# M869D.net
KiCad netlist of a schematic drawn in EAGLE
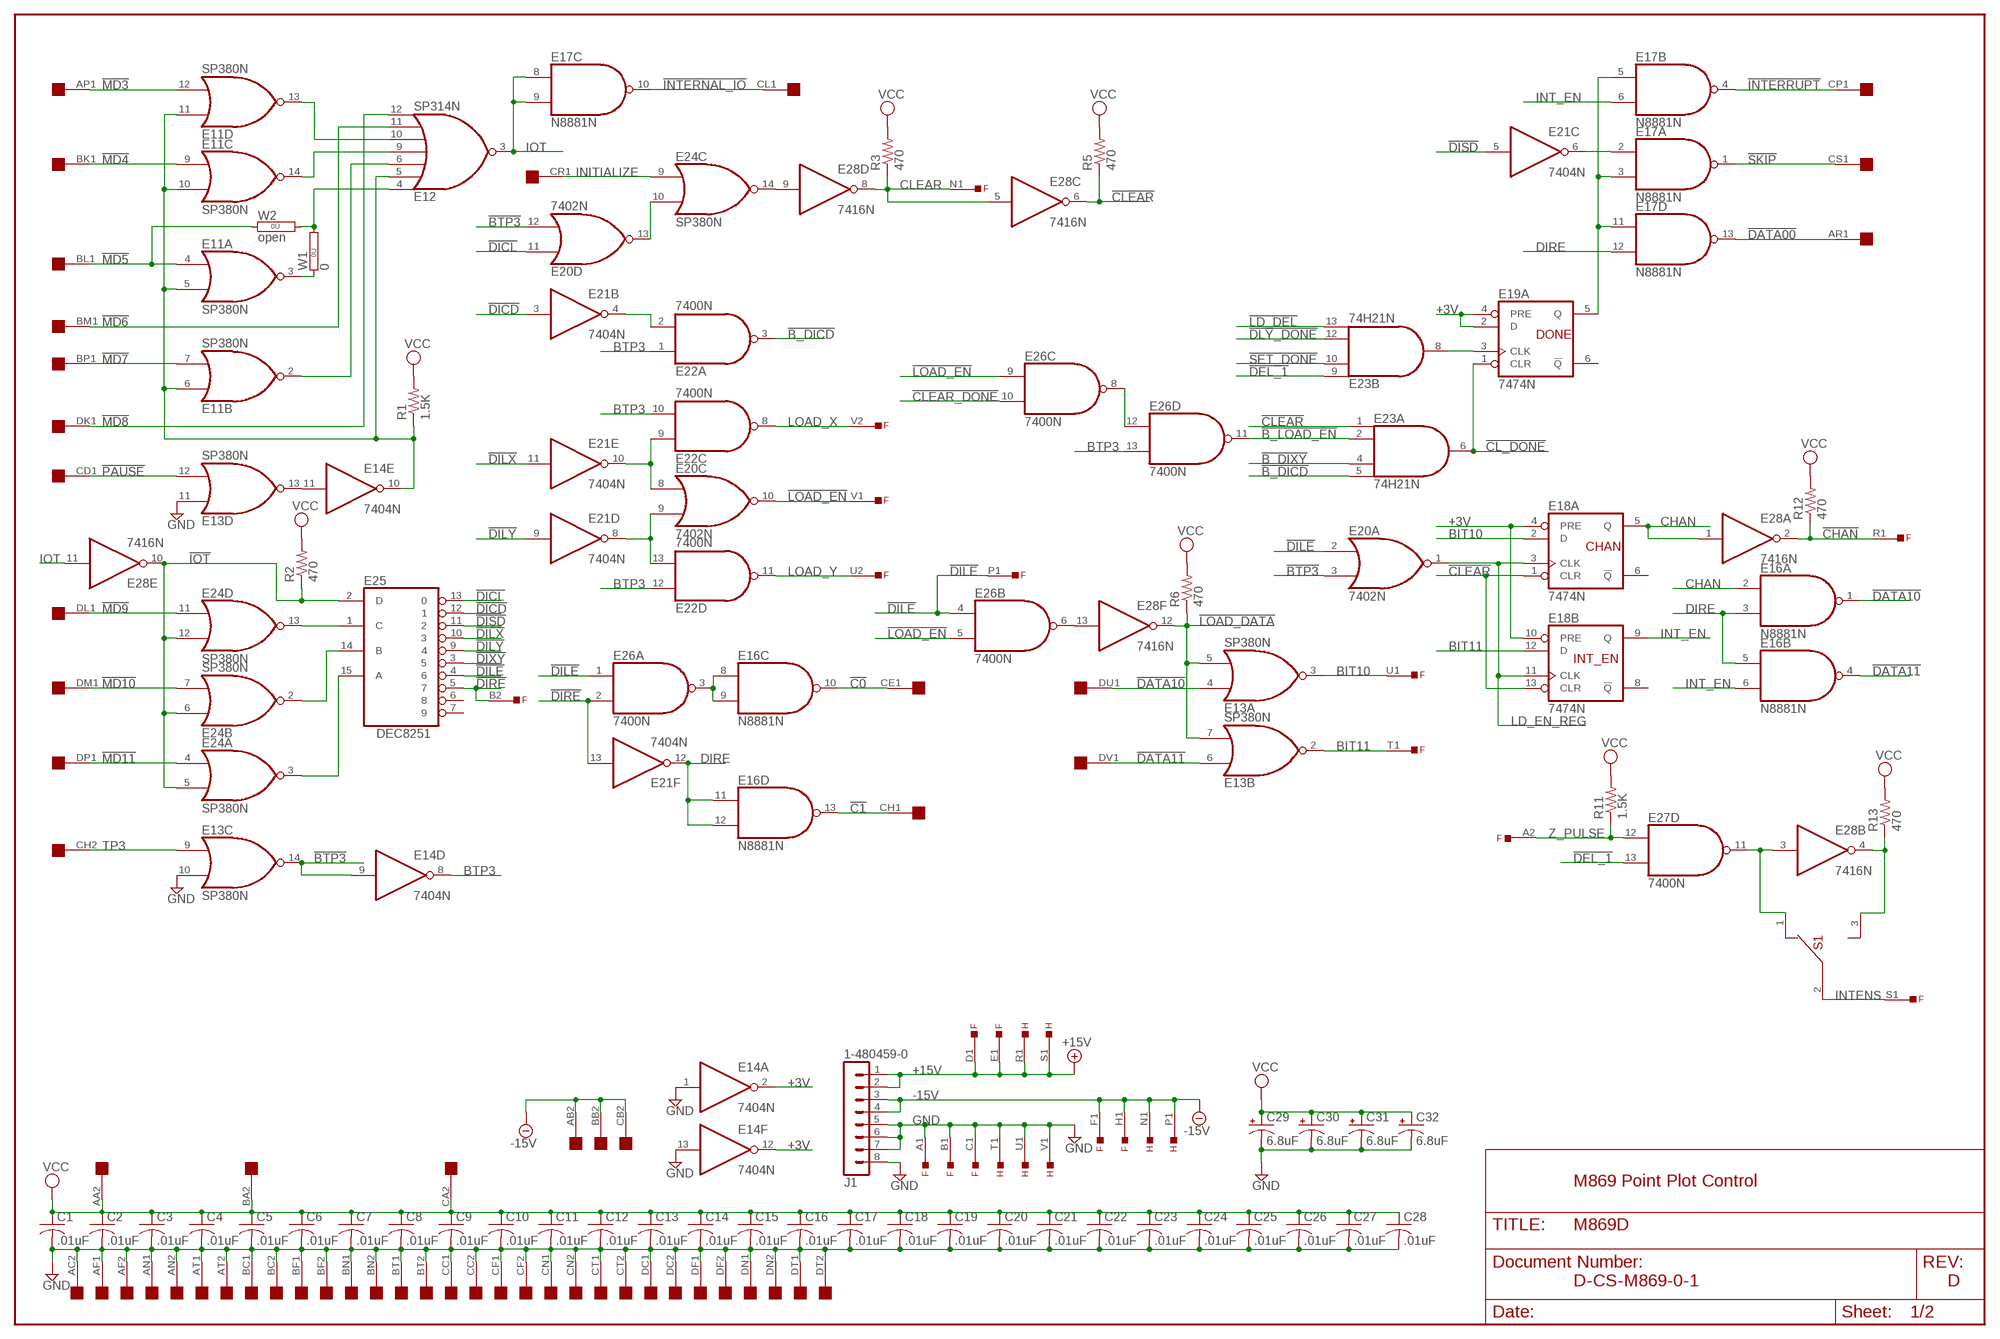
[diagram p0: schematic, sheet 1]
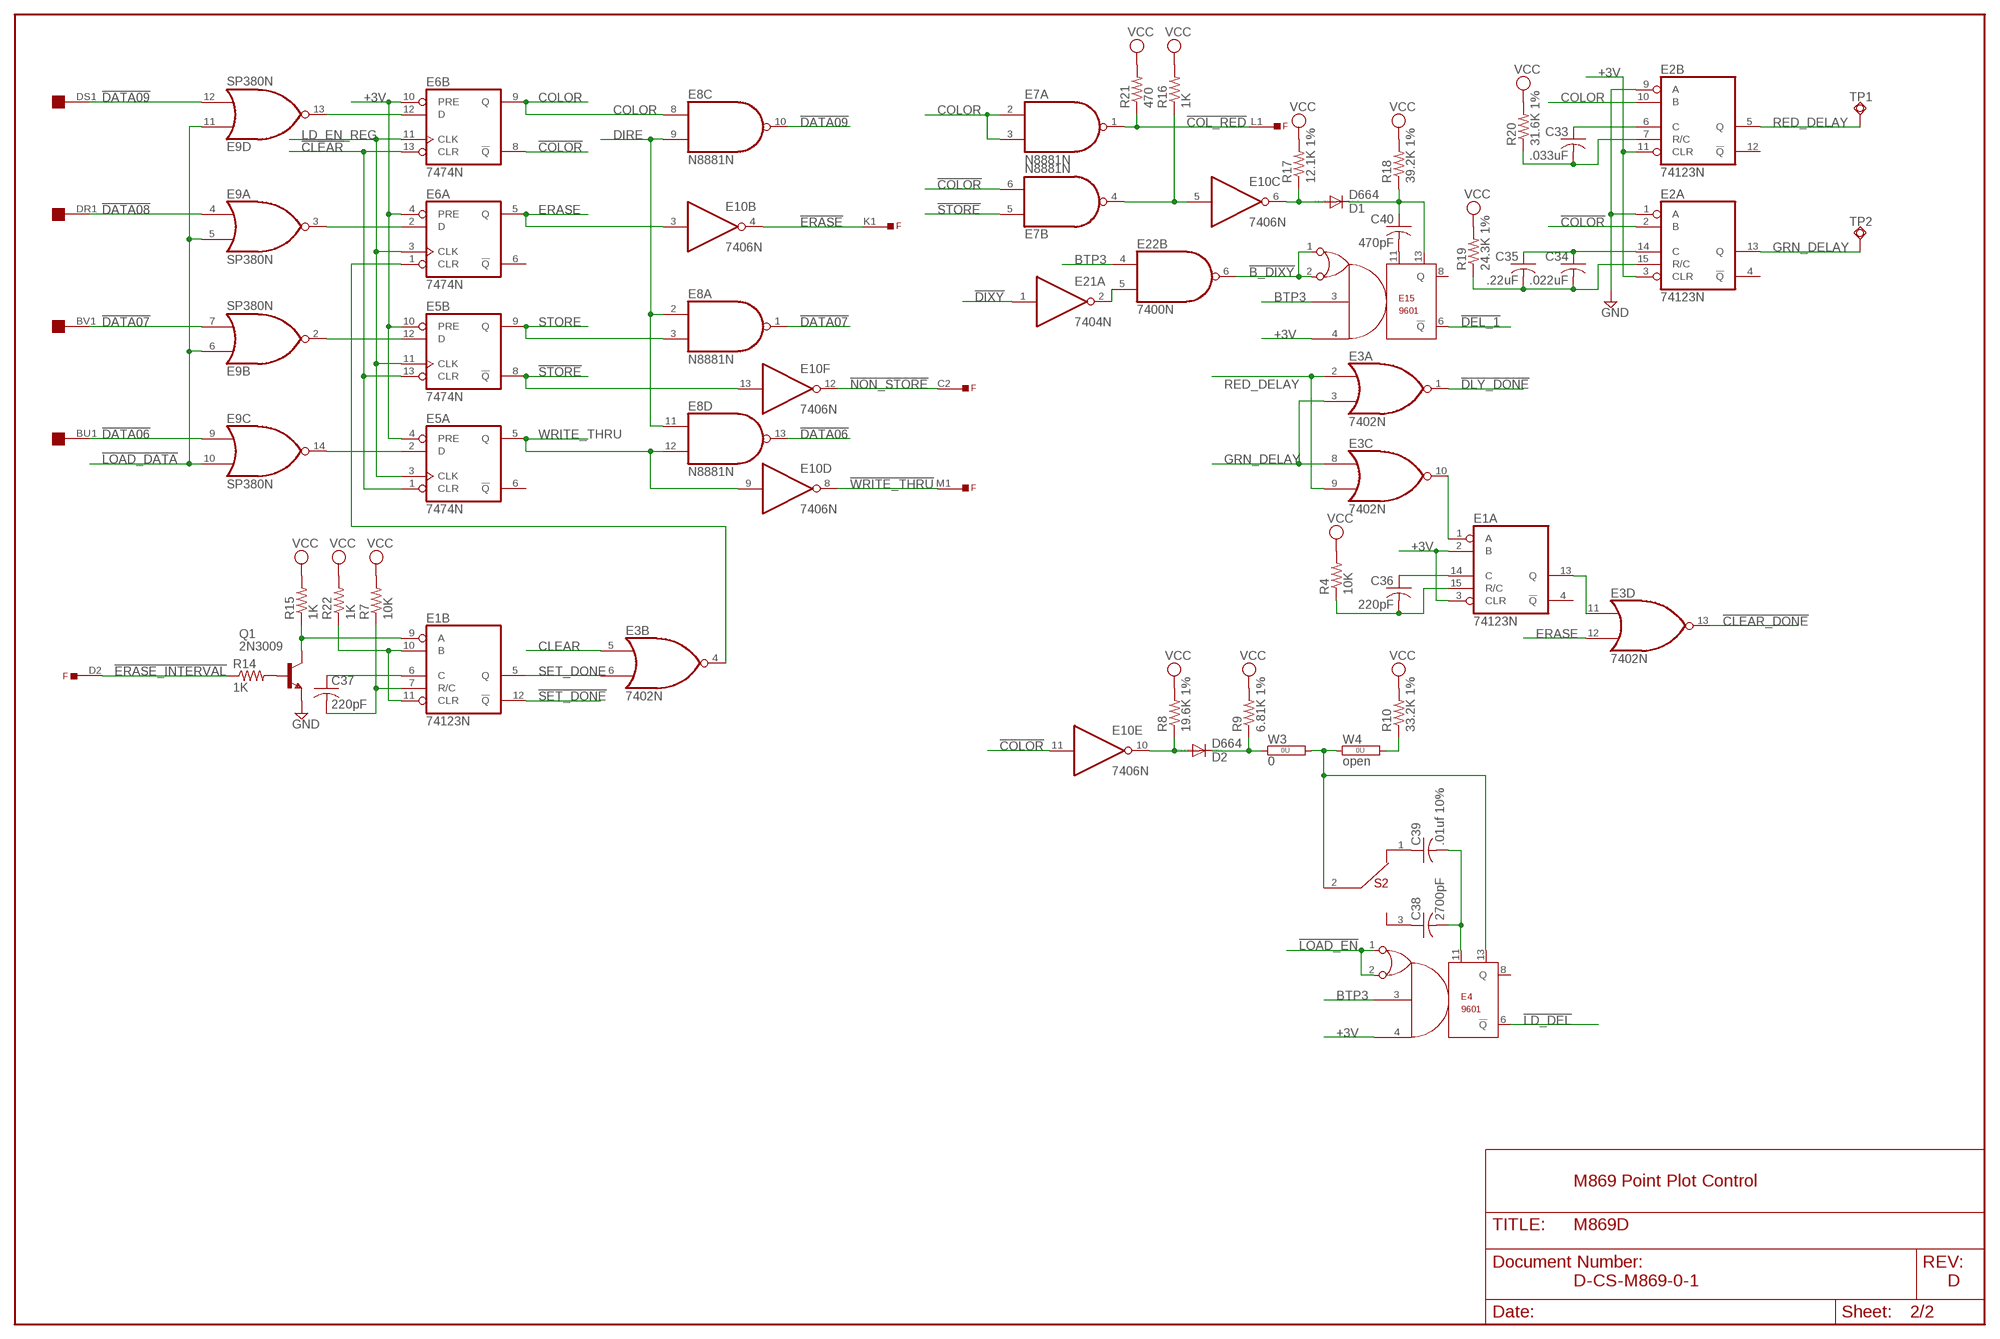
[diagram p1: schematic, sheet 2]

(export (version "E")
  (design (tool "Eeschema 10.0.6"))
  (components
    (comp (ref "C33")
      (value ".033uF")
      (footprint "eagle-import:C325-137X374")
      (libsource (lib "eagle-import") (part "C-US325-137X374"))
    )
    (comp (ref "C34")
      (value ".022uF")
      (footprint "eagle-import:C203-054-229")
      (libsource (lib "eagle-import") (part "C-US8"))
    )
    (comp (ref "C35")
      (value ".22uF")
      (footprint "eagle-import:C203-054-229")
      (libsource (lib "eagle-import") (part "C-US8"))
    )
    (comp (ref "C36")
      (value "220pF")
      (footprint "eagle-import:C063-025X075")
      (libsource (lib "eagle-import") (part "C-US"))
    )
    (comp (ref "C37")
      (value "220pF")
      (footprint "eagle-import:C063-025X075")
      (libsource (lib "eagle-import") (part "C-US"))
    )
    (comp (ref "C38")
      (value "2700pF")
      (footprint "eagle-import:C102-043X133")
      (libsource (lib "eagle-import") (part "C-US102-043X133"))
    )
    (comp (ref "C39")
      (value ".01uf 10%")
      (footprint "eagle-import:C063-025X075")
      (libsource (lib "eagle-import") (part "C-US"))
    )
    (comp (ref "C40")
      (value "470pF")
      (footprint "eagle-import:C063-025X075")
      (libsource (lib "eagle-import") (part "C-US"))
    )
    (comp (ref "D1")
      (value "D664")
      (footprint "eagle-import:DO35-10")
      (libsource (lib "eagle-import") (part "DIODE-DO35-10"))
    )
    (comp (ref "D2")
      (value "D664")
      (footprint "eagle-import:DO35-10")
      (libsource (lib "eagle-import") (part "DIODE-DO35-10"))
    )
    (comp (ref "E1")
      (value "74123N")
      (footprint "eagle-import:DIL16")
      (libsource (lib "eagle-import") (part "74123N"))
    )
    (comp (ref "E2")
      (value "74123N")
      (footprint "eagle-import:DIL16")
      (libsource (lib "eagle-import") (part "74123N"))
    )
    (comp (ref "E3")
      (value "7402N")
      (footprint "eagle-import:DIL14")
      (libsource (lib "eagle-import") (part "7402N"))
    )
    (comp (ref "E4")
      (value "9601")
      (footprint "eagle-import:DIL14")
      (libsource (lib "eagle-import") (part "9601"))
    )
    (comp (ref "E5")
      (value "7474N")
      (footprint "eagle-import:DIL14")
      (libsource (lib "eagle-import") (part "7474NS"))
    )
    (comp (ref "E6")
      (value "7474N")
      (footprint "eagle-import:DIL14")
      (libsource (lib "eagle-import") (part "7474NS"))
    )
    (comp (ref "E7")
      (value "N8881N")
      (footprint "eagle-import:DIL14")
      (libsource (lib "eagle-import") (part "N8881N"))
    )
    (comp (ref "E8")
      (value "N8881N")
      (footprint "eagle-import:DIL14")
      (libsource (lib "eagle-import") (part "N8881N"))
    )
    (comp (ref "E9")
      (value "SP380N")
      (footprint "eagle-import:DIL14")
      (libsource (lib "eagle-import") (part "SP380N"))
    )
    (comp (ref "E10")
      (value "7406N")
      (footprint "eagle-import:DIL14")
      (libsource (lib "eagle-import") (part "7406N"))
    )
    (comp (ref "E15")
      (value "9601")
      (footprint "eagle-import:DIL14")
      (libsource (lib "eagle-import") (part "9601"))
    )
    (comp (ref "E21")
      (value "7404N")
      (footprint "eagle-import:DIL14")
      (libsource (lib "eagle-import") (part "7404N"))
    )
    (comp (ref "E22")
      (value "7400N")
      (footprint "eagle-import:DIL14")
      (libsource (lib "eagle-import") (part "7400N"))
    )
    (comp (ref "F")
      (value "EDGE-TOP")
      (footprint "eagle-import:EDGE-CON2")
      (libsource (lib "eagle-import") (part "EDGE-TOP"))
    )
    (comp (ref "OMNIBUS")
      (value "QUAD")
      (footprint "eagle-import:EDGE-CON8")
      (libsource (lib "eagle-import") (part "QUAD"))
    )
    (comp (ref "Q1")
      (value "2N3009")
      (footprint "eagle-import:TO18-")
      (libsource (lib "eagle-import") (part "-NPN-TO18-"))
    )
    (comp (ref "R4")
      (value "10K")
      (footprint "eagle-import:0207_10")
      (libsource (lib "eagle-import") (part "R-US_0207/10"))
    )
    (comp (ref "R7")
      (value "10K")
      (footprint "eagle-import:0207_10")
      (libsource (lib "eagle-import") (part "R-US_0207/10"))
    )
    (comp (ref "R8")
      (value "19.6K 1%")
      (footprint "eagle-import:0207_15")
      (libsource (lib "eagle-import") (part "R-US_0207/15"))
    )
    (comp (ref "R9")
      (value "6.81K 1%")
      (footprint "eagle-import:0207_15")
      (libsource (lib "eagle-import") (part "R-US_0207/15"))
    )
    (comp (ref "R10")
      (value "33.2K 1%")
      (footprint "eagle-import:0207_15")
      (libsource (lib "eagle-import") (part "R-US_0207/15"))
    )
    (comp (ref "R14")
      (value "1K")
      (footprint "eagle-import:0207_10")
      (libsource (lib "eagle-import") (part "R-US_0207/10"))
    )
    (comp (ref "R15")
      (value "1K")
      (footprint "eagle-import:0207_10")
      (libsource (lib "eagle-import") (part "R-US_0207/10"))
    )
    (comp (ref "R16")
      (value "1K")
      (footprint "eagle-import:0207_10")
      (libsource (lib "eagle-import") (part "R-US_0207/10"))
    )
    (comp (ref "R17")
      (value "12.1K 1%")
      (footprint "eagle-import:0207_15")
      (libsource (lib "eagle-import") (part "R-US_0207/15"))
    )
    (comp (ref "R18")
      (value "39.2K 1%")
      (footprint "eagle-import:0207_15")
      (libsource (lib "eagle-import") (part "R-US_0207/15"))
    )
    (comp (ref "R19")
      (value "24.3K 1%")
      (footprint "eagle-import:0207_15")
      (libsource (lib "eagle-import") (part "R-US_0207/15"))
    )
    (comp (ref "R20")
      (value "31.6K 1%")
      (footprint "eagle-import:0207_15")
      (libsource (lib "eagle-import") (part "R-US_0207/15"))
    )
    (comp (ref "R21")
      (value "470")
      (footprint "eagle-import:0207_10")
      (libsource (lib "eagle-import") (part "R-US_0207/10"))
    )
    (comp (ref "R22")
      (value "1K")
      (footprint "eagle-import:0207_10")
      (libsource (lib "eagle-import") (part "R-US_0207/10"))
    )
    (comp (ref "S2")
      (value "12-09698")
      (footprint "eagle-import:23-021")
      (libsource (lib "eagle-import") (part "12-09698"))
    )
    (comp (ref "TP1")
      (value "TPSQPAD1-17")
      (footprint "eagle-import:P1-17")
      (libsource (lib "eagle-import") (part "TPSQPAD1-17"))
    )
    (comp (ref "TP2")
      (value "TPSQPAD1-17")
      (footprint "eagle-import:P1-17")
      (libsource (lib "eagle-import") (part "TPSQPAD1-17"))
    )
    (comp (ref "W3")
      (value "0")
      (footprint "eagle-import:0R_10")
      (libsource (lib "eagle-import") (part "0R"))
    )
    (comp (ref "W4")
      (value "open")
      (footprint "eagle-import:0R_10")
      (libsource (lib "eagle-import") (part "0R"))
    )
    (comp (ref "C1")
      (value ".01uF")
      (footprint "eagle-import:C063-025X075")
      (libsource (lib "eagle-import") (part "C-US"))
    )
    (comp (ref "C2")
      (value ".01uF")
      (footprint "eagle-import:C063-025X075")
      (libsource (lib "eagle-import") (part "C-US"))
    )
    (comp (ref "C3")
      (value ".01uF")
      (footprint "eagle-import:C063-025X075")
      (libsource (lib "eagle-import") (part "C-US"))
    )
    (comp (ref "C4")
      (value ".01uF")
      (footprint "eagle-import:C063-025X075")
      (libsource (lib "eagle-import") (part "C-US"))
    )
    (comp (ref "C5")
      (value ".01uF")
      (footprint "eagle-import:C063-025X075")
      (libsource (lib "eagle-import") (part "C-US"))
    )
    (comp (ref "C6")
      (value ".01uF")
      (footprint "eagle-import:C063-025X075")
      (libsource (lib "eagle-import") (part "C-US"))
    )
    (comp (ref "C7")
      (value ".01uF")
      (footprint "eagle-import:C063-025X075")
      (libsource (lib "eagle-import") (part "C-US"))
    )
    (comp (ref "C8")
      (value ".01uF")
      (footprint "eagle-import:C063-025X075")
      (libsource (lib "eagle-import") (part "C-US"))
    )
    (comp (ref "C9")
      (value ".01uF")
      (footprint "eagle-import:C063-025X075")
      (libsource (lib "eagle-import") (part "C-US"))
    )
    (comp (ref "C10")
      (value ".01uF")
      (footprint "eagle-import:C063-025X075")
      (libsource (lib "eagle-import") (part "C-US"))
    )
    (comp (ref "C11")
      (value ".01uF")
      (footprint "eagle-import:C063-025X075")
      (libsource (lib "eagle-import") (part "C-US"))
    )
    (comp (ref "C12")
      (value ".01uF")
      (footprint "eagle-import:C063-025X075")
      (libsource (lib "eagle-import") (part "C-US"))
    )
    (comp (ref "C13")
      (value ".01uF")
      (footprint "eagle-import:C063-025X075")
      (libsource (lib "eagle-import") (part "C-US"))
    )
    (comp (ref "C14")
      (value ".01uF")
      (footprint "eagle-import:C063-025X075")
      (libsource (lib "eagle-import") (part "C-US"))
    )
    (comp (ref "C15")
      (value ".01uF")
      (footprint "eagle-import:C063-025X075")
      (libsource (lib "eagle-import") (part "C-US"))
    )
    (comp (ref "C16")
      (value ".01uF")
      (footprint "eagle-import:C063-025X075")
      (libsource (lib "eagle-import") (part "C-US"))
    )
    (comp (ref "C17")
      (value ".01uF")
      (footprint "eagle-import:C063-025X075")
      (libsource (lib "eagle-import") (part "C-US"))
    )
    (comp (ref "C18")
      (value ".01uF")
      (footprint "eagle-import:C063-025X075")
      (libsource (lib "eagle-import") (part "C-US"))
    )
    (comp (ref "C19")
      (value ".01uF")
      (footprint "eagle-import:C063-025X075")
      (libsource (lib "eagle-import") (part "C-US"))
    )
    (comp (ref "C20")
      (value ".01uF")
      (footprint "eagle-import:C063-025X075")
      (libsource (lib "eagle-import") (part "C-US"))
    )
    (comp (ref "C21")
      (value ".01uF")
      (footprint "eagle-import:C063-025X075")
      (libsource (lib "eagle-import") (part "C-US"))
    )
    (comp (ref "C22")
      (value ".01uF")
      (footprint "eagle-import:C063-025X075")
      (libsource (lib "eagle-import") (part "C-US"))
    )
    (comp (ref "C23")
      (value ".01uF")
      (footprint "eagle-import:C063-025X075")
      (libsource (lib "eagle-import") (part "C-US"))
    )
    (comp (ref "C24")
      (value ".01uF")
      (footprint "eagle-import:C063-025X075")
      (libsource (lib "eagle-import") (part "C-US"))
    )
    (comp (ref "C25")
      (value ".01uF")
      (footprint "eagle-import:C063-025X075")
      (libsource (lib "eagle-import") (part "C-US"))
    )
    (comp (ref "C26")
      (value ".01uF")
      (footprint "eagle-import:C063-025X075")
      (libsource (lib "eagle-import") (part "C-US"))
    )
    (comp (ref "C27")
      (value ".01uF")
      (footprint "eagle-import:C063-025X075")
      (libsource (lib "eagle-import") (part "C-US"))
    )
    (comp (ref "C28")
      (value ".01uF")
      (footprint "eagle-import:C063-025X075")
      (libsource (lib "eagle-import") (part "C-US"))
    )
    (comp (ref "C29")
      (value "6.8uF")
      (footprint "eagle-import:E12-8")
      (libsource (lib "eagle-import") (part "CPOL-USE20-8AXIAL"))
    )
    (comp (ref "C30")
      (value "6.8uF")
      (footprint "eagle-import:E12-8")
      (libsource (lib "eagle-import") (part "CPOL-USE20-8AXIAL"))
    )
    (comp (ref "C31")
      (value "6.8uF")
      (footprint "eagle-import:E12-8")
      (libsource (lib "eagle-import") (part "CPOL-USE20-8AXIAL"))
    )
    (comp (ref "C32")
      (value "6.8uF")
      (footprint "eagle-import:E12-8")
      (libsource (lib "eagle-import") (part "CPOL-USE20-8AXIAL"))
    )
    (comp (ref "E11")
      (value "SP380N")
      (footprint "eagle-import:DIL14")
      (libsource (lib "eagle-import") (part "SP380N"))
    )
    (comp (ref "E12")
      (value "SP314N")
      (footprint "eagle-import:DIL14")
      (libsource (lib "eagle-import") (part "SP314N"))
    )
    (comp (ref "E13")
      (value "SP380N")
      (footprint "eagle-import:DIL14")
      (libsource (lib "eagle-import") (part "SP380N"))
    )
    (comp (ref "E14")
      (value "7404N")
      (footprint "eagle-import:DIL14")
      (libsource (lib "eagle-import") (part "7404N"))
    )
    (comp (ref "E16")
      (value "N8881N")
      (footprint "eagle-import:DIL14")
      (libsource (lib "eagle-import") (part "N8881N"))
    )
    (comp (ref "E17")
      (value "N8881N")
      (footprint "eagle-import:DIL14")
      (libsource (lib "eagle-import") (part "N8881N"))
    )
    (comp (ref "E18")
      (value "7474N")
      (footprint "eagle-import:DIL14")
      (libsource (lib "eagle-import") (part "7474NS"))
    )
    (comp (ref "E19")
      (value "7474N")
      (footprint "eagle-import:DIL14")
      (libsource (lib "eagle-import") (part "7474NS"))
    )
    (comp (ref "E20")
      (value "7402N")
      (footprint "eagle-import:DIL14")
      (libsource (lib "eagle-import") (part "7402N"))
    )
    (comp (ref "E23")
      (value "74H21N")
      (footprint "eagle-import:DIL14")
      (libsource (lib "eagle-import") (part "7421NLS"))
    )
    (comp (ref "E24")
      (value "SP380N")
      (footprint "eagle-import:DIL14")
      (libsource (lib "eagle-import") (part "SP380N"))
    )
    (comp (ref "E25")
      (value "DEC8251")
      (footprint "eagle-import:DIL16")
      (libsource (lib "eagle-import") (part "DEC8251"))
    )
    (comp (ref "E26")
      (value "7400N")
      (footprint "eagle-import:DIL14")
      (libsource (lib "eagle-import") (part "7400N"))
    )
    (comp (ref "E27")
      (value "7400N")
      (footprint "eagle-import:DIL14")
      (libsource (lib "eagle-import") (part "7400N"))
    )
    (comp (ref "E28")
      (value "7416N")
      (footprint "eagle-import:DIL14")
      (libsource (lib "eagle-import") (part "7416N"))
    )
    (comp (ref "H")
      (value "EDGE-TOP")
      (footprint "eagle-import:EDGE-CON2")
      (libsource (lib "eagle-import") (part "EDGE-TOP"))
    )
    (comp (ref "J1")
      (value "1-480459-0")
      (footprint "eagle-import:1-480459-0")
      (libsource (lib "eagle-import") (part "1-480459-0"))
    )
    (comp (ref "R1")
      (value "1.5K")
      (footprint "eagle-import:0207_10")
      (libsource (lib "eagle-import") (part "R-US_0207/10"))
    )
    (comp (ref "R2")
      (value "470")
      (footprint "eagle-import:0207_10")
      (libsource (lib "eagle-import") (part "R-US_0207/10"))
    )
    (comp (ref "R3")
      (value "470")
      (footprint "eagle-import:0207_10")
      (libsource (lib "eagle-import") (part "R-US_0207/10"))
    )
    (comp (ref "R5")
      (value "470")
      (footprint "eagle-import:0207_10")
      (libsource (lib "eagle-import") (part "R-US_0207/10"))
    )
    (comp (ref "R6")
      (value "470")
      (footprint "eagle-import:0207_10")
      (libsource (lib "eagle-import") (part "R-US_0207/10"))
    )
    (comp (ref "R11")
      (value "1.5K")
      (footprint "eagle-import:0207_10")
      (libsource (lib "eagle-import") (part "R-US_0207/10"))
    )
    (comp (ref "R12")
      (value "470")
      (footprint "eagle-import:0207_10")
      (libsource (lib "eagle-import") (part "R-US_0207/10"))
    )
    (comp (ref "R13")
      (value "470")
      (footprint "eagle-import:0207_10")
      (libsource (lib "eagle-import") (part "R-US_0207/10"))
    )
    (comp (ref "S1")
      (value "12-09698")
      (footprint "eagle-import:23-021")
      (libsource (lib "eagle-import") (part "12-09698"))
    )
    (comp (ref "W1")
      (value "0")
      (footprint "eagle-import:0R_10")
      (libsource (lib "eagle-import") (part "0R"))
    )
    (comp (ref "W2")
      (value "open")
      (footprint "eagle-import:0R_10")
      (libsource (lib "eagle-import") (part "0R"))
    )
  )
  (nets
    (net (code "1") (name "+3V") (class "Default")
      (node (ref "E1") (pin "2") (pinfunction "B_2") (pintype "input"))
      (node (ref "E1") (pin "3") (pinfunction "CLR_3") (pintype "input"))
      (node (ref "E14") (pin "12") (pinfunction "O_12") (pintype "output"))
      (node (ref "E14") (pin "2") (pinfunction "O_2") (pintype "output"))
      (node (ref "E15") (pin "4") (pinfunction "P$4_4") (pintype "input"))
      (node (ref "E18") (pin "10") (pinfunction "PRE_10") (pintype "input"))
      (node (ref "E18") (pin "4") (pinfunction "PRE_4") (pintype "input"))
      (node (ref "E19") (pin "2") (pinfunction "D_2") (pintype "input"))
      (node (ref "E19") (pin "4") (pinfunction "PRE_4") (pintype "input"))
      (node (ref "E2") (pin "11") (pinfunction "CLR_11") (pintype "input"))
      (node (ref "E2") (pin "3") (pinfunction "CLR_3") (pintype "input"))
      (node (ref "E4") (pin "4") (pinfunction "P$4_4") (pintype "input"))
      (node (ref "E5") (pin "10") (pinfunction "PRE_10") (pintype "input"))
      (node (ref "E5") (pin "4") (pinfunction "PRE_4") (pintype "input"))
      (node (ref "E6") (pin "10") (pinfunction "PRE_10") (pintype "input"))
      (node (ref "E6") (pin "4") (pinfunction "PRE_4") (pintype "input"))
    )
    (net (code "2") (name "+15V") (class "Default")
      (node (ref "F") (pin "D1") (pinfunction "P_D1") (pintype "passive"))
      (node (ref "F") (pin "E1") (pinfunction "P_E1") (pintype "passive"))
      (node (ref "H") (pin "R1") (pinfunction "P_R1") (pintype "passive"))
      (node (ref "H") (pin "S1") (pinfunction "P_S1") (pintype "passive"))
      (node (ref "J1") (pin "1") (pinfunction "1_1") (pintype "passive"))
      (node (ref "J1") (pin "2") (pinfunction "2_2") (pintype "passive"))
    )
    (net (code "3") (name "-15V") (class "Default")
      (node (ref "F") (pin "F1") (pinfunction "P_F1") (pintype "passive"))
      (node (ref "F") (pin "H1") (pinfunction "P_H1") (pintype "passive"))
      (node (ref "H") (pin "N1") (pinfunction "P_N1") (pintype "passive"))
      (node (ref "H") (pin "P1") (pinfunction "P_P1") (pintype "passive"))
      (node (ref "J1") (pin "3") (pinfunction "3_3") (pintype "passive"))
      (node (ref "J1") (pin "4") (pinfunction "4_4") (pintype "passive"))
      (node (ref "OMNIBUS") (pin "AB2") (pinfunction "1_AB2") (pintype "bidirectional"))
      (node (ref "OMNIBUS") (pin "BB2") (pinfunction "1_BB2") (pintype "bidirectional"))
      (node (ref "OMNIBUS") (pin "CB2") (pinfunction "1_CB2") (pintype "bidirectional"))
    )
    (net (code "4") (name "BIT10") (class "Default")
      (node (ref "E13") (pin "3") (pinfunction "O_3") (pintype "output"))
      (node (ref "E18") (pin "2") (pinfunction "D_2") (pintype "input"))
      (node (ref "F") (pin "U1") (pinfunction "P_U1") (pintype "passive"))
    )
    (net (code "5") (name "BIT11") (class "Default")
      (node (ref "E13") (pin "2") (pinfunction "O_2") (pintype "output"))
      (node (ref "E18") (pin "12") (pinfunction "D_12") (pintype "input"))
      (node (ref "F") (pin "T1") (pinfunction "P_T1") (pintype "passive"))
    )
    (net (code "6") (name "BTP3") (class "Default")
      (node (ref "E14") (pin "8") (pinfunction "O_8") (pintype "output"))
      (node (ref "E15") (pin "3") (pinfunction "P$3_3") (pintype "input"))
      (node (ref "E22") (pin "1") (pinfunction "I0_1") (pintype "input"))
      (node (ref "E22") (pin "10") (pinfunction "I1_10") (pintype "input"))
      (node (ref "E22") (pin "12") (pinfunction "I0_12") (pintype "input"))
      (node (ref "E22") (pin "4") (pinfunction "I0_4") (pintype "input"))
      (node (ref "E26") (pin "13") (pinfunction "I1_13") (pintype "input"))
      (node (ref "E4") (pin "3") (pinfunction "P$3_3") (pintype "input"))
    )
    (net (code "7") (name "CHAN") (class "Default")
      (node (ref "E16") (pin "2") (pinfunction "I0_2") (pintype "input"))
      (node (ref "E18") (pin "5") (pinfunction "Q_5") (pintype "output"))
      (node (ref "E28") (pin "1") (pinfunction "I_1") (pintype "input"))
    )
    (net (code "8") (name "CLEAR") (class "Default")
      (node (ref "E28") (pin "5") (pinfunction "I_5") (pintype "input"))
      (node (ref "E28") (pin "8") (pinfunction "O_8") (pintype "open_collector"))
      (node (ref "E3") (pin "5") (pinfunction "I0_5") (pintype "input"))
      (node (ref "F") (pin "N1") (pinfunction "P_N1") (pintype "passive"))
      (node (ref "R3") (pin "1") (pinfunction "1_1") (pintype "passive"))
    )
    (net (code "9") (name "COLOR") (class "Default")
      (node (ref "E2") (pin "10") (pinfunction "B_10") (pintype "input"))
      (node (ref "E6") (pin "9") (pinfunction "Q_9") (pintype "output"))
      (node (ref "E7") (pin "2") (pinfunction "I0_2") (pintype "input"))
      (node (ref "E7") (pin "3") (pinfunction "I1_3") (pintype "input"))
      (node (ref "E8") (pin "8") (pinfunction "I0_8") (pintype "input"))
    )
    (net (code "10") (name "DIRE") (class "Default")
      (node (ref "E16") (pin "11") (pinfunction "I0_11") (pintype "input"))
      (node (ref "E16") (pin "12") (pinfunction "I1_12") (pintype "input"))
      (node (ref "E16") (pin "3") (pinfunction "I1_3") (pintype "input"))
      (node (ref "E16") (pin "5") (pinfunction "I0_5") (pintype "input"))
      (node (ref "E17") (pin "12") (pinfunction "I1_12") (pintype "input"))
      (node (ref "E21") (pin "12") (pinfunction "O_12") (pintype "output"))
      (node (ref "E8") (pin "11") (pinfunction "I0_11") (pintype "input"))
      (node (ref "E8") (pin "2") (pinfunction "I0_2") (pintype "input"))
      (node (ref "E8") (pin "9") (pinfunction "I1_9") (pintype "input"))
    )
    (net (code "11") (name "ERASE") (class "Default")
      (node (ref "E10") (pin "3") (pinfunction "I_3") (pintype "input"))
      (node (ref "E3") (pin "12") (pinfunction "I1_12") (pintype "input"))
      (node (ref "E6") (pin "5") (pinfunction "Q_5") (pintype "output"))
    )
    (net (code "12") (name "GND") (class "Default")
      (node (ref "C1") (pin "2") (pinfunction "2_2") (pintype "passive"))
      (node (ref "C10") (pin "2") (pinfunction "2_2") (pintype "passive"))
      (node (ref "C11") (pin "2") (pinfunction "2_2") (pintype "passive"))
      (node (ref "C12") (pin "2") (pinfunction "2_2") (pintype "passive"))
      (node (ref "C13") (pin "2") (pinfunction "2_2") (pintype "passive"))
      (node (ref "C14") (pin "2") (pinfunction "2_2") (pintype "passive"))
      (node (ref "C15") (pin "2") (pinfunction "2_2") (pintype "passive"))
      (node (ref "C16") (pin "2") (pinfunction "2_2") (pintype "passive"))
      (node (ref "C17") (pin "2") (pinfunction "2_2") (pintype "passive"))
      (node (ref "C18") (pin "2") (pinfunction "2_2") (pintype "passive"))
      (node (ref "C19") (pin "2") (pinfunction "2_2") (pintype "passive"))
      (node (ref "C2") (pin "2") (pinfunction "2_2") (pintype "passive"))
      (node (ref "C20") (pin "2") (pinfunction "2_2") (pintype "passive"))
      (node (ref "C21") (pin "2") (pinfunction "2_2") (pintype "passive"))
      (node (ref "C22") (pin "2") (pinfunction "2_2") (pintype "passive"))
      (node (ref "C23") (pin "2") (pinfunction "2_2") (pintype "passive"))
      (node (ref "C24") (pin "2") (pinfunction "2_2") (pintype "passive"))
      (node (ref "C25") (pin "2") (pinfunction "2_2") (pintype "passive"))
      (node (ref "C26") (pin "2") (pinfunction "2_2") (pintype "passive"))
      (node (ref "C27") (pin "2") (pinfunction "2_2") (pintype "passive"))
      (node (ref "C28") (pin "2") (pinfunction "2_2") (pintype "passive"))
      (node (ref "C29") (pin "-") (pinfunction "-_-") (pintype "passive"))
      (node (ref "C3") (pin "2") (pinfunction "2_2") (pintype "passive"))
      (node (ref "C30") (pin "-") (pinfunction "-_-") (pintype "passive"))
      (node (ref "C31") (pin "-") (pinfunction "-_-") (pintype "passive"))
      (node (ref "C32") (pin "-") (pinfunction "-_-") (pintype "passive"))
      (node (ref "C4") (pin "2") (pinfunction "2_2") (pintype "passive"))
      (node (ref "C5") (pin "2") (pinfunction "2_2") (pintype "passive"))
      (node (ref "C6") (pin "2") (pinfunction "2_2") (pintype "passive"))
      (node (ref "C7") (pin "2") (pinfunction "2_2") (pintype "passive"))
      (node (ref "C8") (pin "2") (pinfunction "2_2") (pintype "passive"))
      (node (ref "C9") (pin "2") (pinfunction "2_2") (pintype "passive"))
      (node (ref "E13") (pin "10") (pinfunction "I1_10") (pintype "input"))
      (node (ref "E13") (pin "11") (pinfunction "I0_11") (pintype "input"))
      (node (ref "E14") (pin "1") (pinfunction "I_1") (pintype "input"))
      (node (ref "E14") (pin "13") (pinfunction "I_13") (pintype "input"))
      (node (ref "E2") (pin "1") (pinfunction "A_1") (pintype "input"))
      (node (ref "E2") (pin "9") (pinfunction "A_9") (pintype "input"))
      (node (ref "F") (pin "A1") (pinfunction "P_A1") (pintype "passive"))
      (node (ref "F") (pin "B1") (pinfunction "P_B1") (pintype "passive"))
      (node (ref "F") (pin "C1") (pinfunction "P_C1") (pintype "passive"))
      (node (ref "H") (pin "T1") (pinfunction "P_T1") (pintype "passive"))
      (node (ref "H") (pin "U1") (pinfunction "P_U1") (pintype "passive"))
      (node (ref "H") (pin "V1") (pinfunction "P_V1") (pintype "passive"))
      (node (ref "J1") (pin "5") (pinfunction "5_5") (pintype "passive"))
      (node (ref "J1") (pin "6") (pinfunction "6_6") (pintype "passive"))
      (node (ref "J1") (pin "7") (pinfunction "7_7") (pintype "passive"))
      (node (ref "J1") (pin "8") (pinfunction "8_8") (pintype "passive"))
      (node (ref "OMNIBUS") (pin "AC2") (pinfunction "1_AC2") (pintype "bidirectional"))
      (node (ref "OMNIBUS") (pin "AF1") (pinfunction "1_AF1") (pintype "bidirectional"))
      (node (ref "OMNIBUS") (pin "AF2") (pinfunction "1_AF2") (pintype "bidirectional"))
      (node (ref "OMNIBUS") (pin "AN1") (pinfunction "1_AN1") (pintype "bidirectional"))
      (node (ref "OMNIBUS") (pin "AN2") (pinfunction "1_AN2") (pintype "bidirectional"))
      (node (ref "OMNIBUS") (pin "AT1") (pinfunction "1_AT1") (pintype "bidirectional"))
      (node (ref "OMNIBUS") (pin "AT2") (pinfunction "1_AT2") (pintype "bidirectional"))
      (node (ref "OMNIBUS") (pin "BC1") (pinfunction "1_BC1") (pintype "bidirectional"))
      (node (ref "OMNIBUS") (pin "BC2") (pinfunction "1_BC2") (pintype "bidirectional"))
      (node (ref "OMNIBUS") (pin "BF1") (pinfunction "1_BF1") (pintype "bidirectional"))
      (node (ref "OMNIBUS") (pin "BF2") (pinfunction "1_BF2") (pintype "bidirectional"))
      (node (ref "OMNIBUS") (pin "BN1") (pinfunction "1_BN1") (pintype "bidirectional"))
      (node (ref "OMNIBUS") (pin "BN2") (pinfunction "1_BN2") (pintype "bidirectional"))
      (node (ref "OMNIBUS") (pin "BT1") (pinfunction "1_BT1") (pintype "bidirectional"))
      (node (ref "OMNIBUS") (pin "BT2") (pinfunction "1_BT2") (pintype "bidirectional"))
      (node (ref "OMNIBUS") (pin "CC1") (pinfunction "1_CC1") (pintype "bidirectional"))
      (node (ref "OMNIBUS") (pin "CC2") (pinfunction "1_CC2") (pintype "bidirectional"))
      (node (ref "OMNIBUS") (pin "CF1") (pinfunction "1_CF1") (pintype "bidirectional"))
      (node (ref "OMNIBUS") (pin "CF2") (pinfunction "1_CF2") (pintype "bidirectional"))
      (node (ref "OMNIBUS") (pin "CN1") (pinfunction "1_CN1") (pintype "bidirectional"))
      (node (ref "OMNIBUS") (pin "CN2") (pinfunction "1_CN2") (pintype "bidirectional"))
      (node (ref "OMNIBUS") (pin "CT1") (pinfunction "1_CT1") (pintype "bidirectional"))
      (node (ref "OMNIBUS") (pin "CT2") (pinfunction "1_CT2") (pintype "bidirectional"))
      (node (ref "OMNIBUS") (pin "DC1") (pinfunction "1_DC1") (pintype "bidirectional"))
      (node (ref "OMNIBUS") (pin "DC2") (pinfunction "1_DC2") (pintype "bidirectional"))
      (node (ref "OMNIBUS") (pin "DF1") (pinfunction "1_DF1") (pintype "bidirectional"))
      (node (ref "OMNIBUS") (pin "DF2") (pinfunction "1_DF2") (pintype "bidirectional"))
      (node (ref "OMNIBUS") (pin "DN1") (pinfunction "1_DN1") (pintype "bidirectional"))
      (node (ref "OMNIBUS") (pin "DN2") (pinfunction "1_DN2") (pintype "bidirectional"))
      (node (ref "OMNIBUS") (pin "DT1") (pinfunction "1_DT1") (pintype "bidirectional"))
      (node (ref "OMNIBUS") (pin "DT2") (pinfunction "1_DT2") (pintype "bidirectional"))
      (node (ref "Q1") (pin "1") (pinfunction "E_1") (pintype "passive"))
    )
    (net (code "13") (name "GRN_DELAY") (class "Default")
      (node (ref "E2") (pin "13") (pinfunction "Q_13") (pintype "output"))
      (node (ref "E3") (pin "3") (pinfunction "I1_3") (pintype "input"))
      (node (ref "E3") (pin "8") (pinfunction "I0_8") (pintype "input"))
      (node (ref "TP2") (pin "TP") (pinfunction "TP_TP") (pintype "input"))
    )
    (net (code "14") (name "INITIALIZE") (class "Default")
      (node (ref "E24") (pin "9") (pinfunction "I0_9") (pintype "input"))
      (node (ref "OMNIBUS") (pin "CR1") (pinfunction "1_CR1") (pintype "bidirectional"))
    )
    (net (code "15") (name "INTENS") (class "Default")
      (node (ref "F") (pin "S1") (pinfunction "P_S1") (pintype "passive"))
      (node (ref "S1") (pin "2") (pinfunction "A2_2") (pintype "bidirectional"))
    )
    (net (code "16") (name "INT_EN") (class "Default")
      (node (ref "E16") (pin "6") (pinfunction "I1_6") (pintype "input"))
      (node (ref "E17") (pin "6") (pinfunction "I1_6") (pintype "input"))
      (node (ref "E18") (pin "9") (pinfunction "Q_9") (pintype "output"))
    )
    (net (code "17") (name "IOT") (class "Default")
      (node (ref "E12") (pin "3") (pinfunction "O_3") (pintype "output"))
      (node (ref "E17") (pin "8") (pinfunction "I0_8") (pintype "input"))
      (node (ref "E17") (pin "9") (pinfunction "I1_9") (pintype "input"))
      (node (ref "E28") (pin "11") (pinfunction "I_11") (pintype "input"))
    )
    (net (code "18") (name "LD_EN_REG") (class "Default")
      (node (ref "E18") (pin "11") (pinfunction "CLK_11") (pintype "input"))
      (node (ref "E18") (pin "3") (pinfunction "CLK_3") (pintype "input"))
      (node (ref "E20") (pin "1") (pinfunction "O_1") (pintype "output"))
      (node (ref "E5") (pin "11") (pinfunction "CLK_11") (pintype "input"))
      (node (ref "E5") (pin "3") (pinfunction "CLK_3") (pintype "input"))
      (node (ref "E6") (pin "11") (pinfunction "CLK_11") (pintype "input"))
      (node (ref "E6") (pin "3") (pinfunction "CLK_3") (pintype "input"))
    )
    (net (code "19") (name "LOAD_X") (class "Default")
      (node (ref "E22") (pin "8") (pinfunction "O_8") (pintype "output"))
      (node (ref "F") (pin "V2") (pinfunction "P_V2") (pintype "passive"))
    )
    (net (code "20") (name "LOAD_Y") (class "Default")
      (node (ref "E22") (pin "11") (pinfunction "O_11") (pintype "output"))
      (node (ref "F") (pin "U2") (pinfunction "P_U2") (pintype "passive"))
    )
    (net (code "21") (name "Net-(D2-PadC)") (class "Default")
      (node (ref "D2") (pin "C") (pinfunction "C_C") (pintype "passive"))
      (node (ref "R9") (pin "1") (pinfunction "1_1") (pintype "passive"))
      (node (ref "W3") (pin "1") (pinfunction "1_1") (pintype "passive"))
    )
    (net (code "22") (name "Net-(E1A-A)") (class "Default")
      (node (ref "E1") (pin "1") (pinfunction "A_1") (pintype "input"))
      (node (ref "E3") (pin "10") (pinfunction "O_10") (pintype "output"))
    )
    (net (code "23") (name "Net-(E1A-C)") (class "Default")
      (node (ref "C36") (pin "1") (pinfunction "1_1") (pintype "passive"))
      (node (ref "E1") (pin "14") (pinfunction "C_14") (pintype "input"))
    )
    (net (code "24") (name "Net-(E1A-Q)") (class "Default")
      (node (ref "E1") (pin "13") (pinfunction "Q_13") (pintype "output"))
      (node (ref "E3") (pin "11") (pinfunction "I0_11") (pintype "input"))
    )
    (net (code "25") (name "Net-(E1A-R{slash}C)") (class "Default")
      (node (ref "C36") (pin "2") (pinfunction "2_2") (pintype "passive"))
      (node (ref "E1") (pin "15") (pinfunction "R/C_15") (pintype "input"))
      (node (ref "R4") (pin "1") (pinfunction "1_1") (pintype "passive"))
    )
    (net (code "26") (name "Net-(E1B-A)") (class "Default")
      (node (ref "E1") (pin "9") (pinfunction "A_9") (pintype "input"))
      (node (ref "Q1") (pin "3") (pinfunction "C_3") (pintype "passive"))
      (node (ref "R15") (pin "1") (pinfunction "1_1") (pintype "passive"))
    )
    (net (code "27") (name "Net-(E1B-B)") (class "Default")
      (node (ref "E1") (pin "10") (pinfunction "B_10") (pintype "input"))
      (node (ref "E1") (pin "11") (pinfunction "CLR_11") (pintype "input"))
      (node (ref "R22") (pin "1") (pinfunction "1_1") (pintype "passive"))
    )
    (net (code "28") (name "Net-(E1B-C)") (class "Default")
      (node (ref "C37") (pin "1") (pinfunction "1_1") (pintype "passive"))
      (node (ref "E1") (pin "6") (pinfunction "C_6") (pintype "input"))
    )
    (net (code "29") (name "Net-(E1B-R{slash}C)") (class "Default")
      (node (ref "C37") (pin "2") (pinfunction "2_2") (pintype "passive"))
      (node (ref "E1") (pin "7") (pinfunction "R/C_7") (pintype "input"))
      (node (ref "R7") (pin "1") (pinfunction "1_1") (pintype "passive"))
    )
    (net (code "30") (name "Net-(E2A-C)") (class "Default")
      (node (ref "C34") (pin "1") (pinfunction "1_1") (pintype "passive"))
      (node (ref "C35") (pin "1") (pinfunction "1_1") (pintype "passive"))
      (node (ref "E2") (pin "14") (pinfunction "C_14") (pintype "input"))
    )
    (net (code "31") (name "Net-(E2A-R{slash}C)") (class "Default")
      (node (ref "C34") (pin "2") (pinfunction "2_2") (pintype "passive"))
      (node (ref "C35") (pin "2") (pinfunction "2_2") (pintype "passive"))
      (node (ref "E2") (pin "15") (pinfunction "R/C_15") (pintype "input"))
      (node (ref "R19") (pin "1") (pinfunction "1_1") (pintype "passive"))
    )
    (net (code "32") (name "Net-(E2B-C)") (class "Default")
      (node (ref "C33") (pin "1") (pinfunction "1_1") (pintype "passive"))
      (node (ref "E2") (pin "6") (pinfunction "C_6") (pintype "input"))
    )
    (net (code "33") (name "Net-(E2B-R{slash}C)") (class "Default")
      (node (ref "C33") (pin "2") (pinfunction "2_2") (pintype "passive"))
      (node (ref "E2") (pin "7") (pinfunction "R/C_7") (pintype "input"))
      (node (ref "R20") (pin "1") (pinfunction "1_1") (pintype "passive"))
    )
    (net (code "34") (name "Net-(E3B-O)") (class "Default")
      (node (ref "E3") (pin "4") (pinfunction "O_4") (pintype "output"))
      (node (ref "E6") (pin "1") (pinfunction "CLR_1") (pintype "input"))
    )
    (net (code "35") (name "Net-(E4A-P$5)") (class "Default")
      (node (ref "C38") (pin "2") (pinfunction "2_2") (pintype "passive"))
      (node (ref "C39") (pin "2") (pinfunction "2_2") (pintype "passive"))
      (node (ref "E4") (pin "11") (pinfunction "P$5_11") (pintype "bidirectional"))
    )
    (net (code "36") (name "Net-(E4A-P$6)") (class "Default")
      (node (ref "E4") (pin "13") (pinfunction "P$6_13") (pintype "bidirectional"))
      (node (ref "S2") (pin "2") (pinfunction "A2_2") (pintype "bidirectional"))
      (node (ref "W3") (pin "2") (pinfunction "2_2") (pintype "passive"))
      (node (ref "W4") (pin "1") (pinfunction "1_1") (pintype "passive"))
    )
    (net (code "37") (name "Net-(E5A-D)") (class "Default")
      (node (ref "E5") (pin "2") (pinfunction "D_2") (pintype "input"))
      (node (ref "E9") (pin "14") (pinfunction "O_14") (pintype "output"))
    )
    (net (code "38") (name "Net-(E5B-D)") (class "Default")
      (node (ref "E5") (pin "12") (pinfunction "D_12") (pintype "input"))
      (node (ref "E9") (pin "2") (pinfunction "O_2") (pintype "output"))
    )
    (net (code "39") (name "Net-(E6A-D)") (class "Default")
      (node (ref "E6") (pin "2") (pinfunction "D_2") (pintype "input"))
      (node (ref "E9") (pin "3") (pinfunction "O_3") (pintype "output"))
    )
    (net (code "40") (name "Net-(E6B-D)") (class "Default")
      (node (ref "E6") (pin "12") (pinfunction "D_12") (pintype "input"))
      (node (ref "E9") (pin "13") (pinfunction "O_13") (pintype "output"))
    )
    (net (code "41") (name "Net-(E10C-I)") (class "Default")
      (node (ref "E10") (pin "5") (pinfunction "I_5") (pintype "input"))
      (node (ref "E7") (pin "4") (pinfunction "O_4") (pintype "open_collector"))
      (node (ref "R16") (pin "1") (pinfunction "1_1") (pintype "passive"))
    )
    (net (code "42") (name "Net-(E10C-O)") (class "Default")
      (node (ref "D1") (pin "A") (pinfunction "A_A") (pintype "passive"))
      (node (ref "E10") (pin "6") (pinfunction "O_6") (pintype "open_collector"))
      (node (ref "R17") (pin "1") (pinfunction "1_1") (pintype "passive"))
    )
    (net (code "43") (name "Net-(E10E-O)") (class "Default")
      (node (ref "D2") (pin "A") (pinfunction "A_A") (pintype "passive"))
      (node (ref "E10") (pin "10") (pinfunction "O_10") (pintype "open_collector"))
      (node (ref "R8") (pin "1") (pinfunction "1_1") (pintype "passive"))
    )
    (net (code "44") (name "Net-(E11A-I1)") (class "Default")
      (node (ref "E11") (pin "10") (pinfunction "I1_10") (pintype "input"))
      (node (ref "E11") (pin "11") (pinfunction "I0_11") (pintype "input"))
      (node (ref "E11") (pin "5") (pinfunction "I1_5") (pintype "input"))
      (node (ref "E11") (pin "6") (pinfunction "I0_6") (pintype "input"))
      (node (ref "E12") (pin "5") (pinfunction "I1_5") (pintype "input"))
      (node (ref "E14") (pin "10") (pinfunction "O_10") (pintype "output"))
      (node (ref "R1") (pin "1") (pinfunction "1_1") (pintype "passive"))
    )
    (net (code "45") (name "Net-(E11A-O)") (class "Default")
      (node (ref "E11") (pin "3") (pinfunction "O_3") (pintype "output"))
      (node (ref "W1") (pin "1") (pinfunction "1_1") (pintype "passive"))
    )
    (net (code "46") (name "Net-(E11B-O)") (class "Default")
      (node (ref "E11") (pin "2") (pinfunction "O_2") (pintype "output"))
      (node (ref "E12") (pin "6") (pinfunction "I2_6") (pintype "input"))
    )
    (net (code "47") (name "Net-(E11C-O)") (class "Default")
      (node (ref "E11") (pin "14") (pinfunction "O_14") (pintype "output"))
      (node (ref "E12") (pin "9") (pinfunction "I3_9") (pintype "input"))
    )
    (net (code "48") (name "Net-(E11D-O)") (class "Default")
      (node (ref "E11") (pin "13") (pinfunction "O_13") (pintype "output"))
      (node (ref "E12") (pin "10") (pinfunction "I4_10") (pintype "input"))
    )
    (net (code "49") (name "Net-(E12A-I0)") (class "Default")
      (node (ref "E12") (pin "4") (pinfunction "I0_4") (pintype "input"))
      (node (ref "W1") (pin "2") (pinfunction "2_2") (pintype "passive"))
      (node (ref "W2") (pin "2") (pinfunction "2_2") (pintype "passive"))
    )
    (net (code "50") (name "Net-(E13D-O)") (class "Default")
      (node (ref "E13") (pin "13") (pinfunction "O_13") (pintype "output"))
      (node (ref "E14") (pin "11") (pinfunction "I_11") (pintype "input"))
    )
    (net (code "51") (name "Net-(E15A-P$5)") (class "Default")
      (node (ref "C40") (pin "2") (pinfunction "2_2") (pintype "passive"))
      (node (ref "E15") (pin "11") (pinfunction "P$5_11") (pintype "bidirectional"))
    )
    (net (code "52") (name "Net-(E15A-P$6)") (class "Default")
      (node (ref "C40") (pin "1") (pinfunction "1_1") (pintype "passive"))
      (node (ref "D1") (pin "C") (pinfunction "C_C") (pintype "passive"))
      (node (ref "E15") (pin "13") (pinfunction "P$6_13") (pintype "bidirectional"))
      (node (ref "R18") (pin "1") (pinfunction "1_1") (pintype "passive"))
    )
    (net (code "53") (name "Net-(E16C-I0)") (class "Default")
      (node (ref "E16") (pin "8") (pinfunction "I0_8") (pintype "input"))
      (node (ref "E16") (pin "9") (pinfunction "I1_9") (pintype "input"))
      (node (ref "E26") (pin "3") (pinfunction "O_3") (pintype "output"))
    )
    (net (code "54") (name "Net-(E17A-I0)") (class "Default")
      (node (ref "E17") (pin "2") (pinfunction "I0_2") (pintype "input"))
      (node (ref "E21") (pin "6") (pinfunction "O_6") (pintype "output"))
    )
    (net (code "55") (name "Net-(E17A-I1)") (class "Default")
      (node (ref "E17") (pin "11") (pinfunction "I0_11") (pintype "input"))
      (node (ref "E17") (pin "3") (pinfunction "I1_3") (pintype "input"))
      (node (ref "E17") (pin "5") (pinfunction "I0_5") (pintype "input"))
      (node (ref "E19") (pin "5") (pinfunction "Q_5") (pintype "output"))
    )
    (net (code "56") (name "Net-(E19A-CLK)") (class "Default")
      (node (ref "E19") (pin "3") (pinfunction "CLK_3") (pintype "input"))
      (node (ref "E23") (pin "8") (pinfunction "O_8") (pintype "output"))
    )
    (net (code "57") (name "Net-(E20C-I0)") (class "Default")
      (node (ref "E20") (pin "8") (pinfunction "I0_8") (pintype "input"))
      (node (ref "E21") (pin "10") (pinfunction "O_10") (pintype "output"))
      (node (ref "E22") (pin "9") (pinfunction "I0_9") (pintype "input"))
    )
    (net (code "58") (name "Net-(E20C-I1)") (class "Default")
      (node (ref "E20") (pin "9") (pinfunction "I1_9") (pintype "input"))
      (node (ref "E21") (pin "8") (pinfunction "O_8") (pintype "output"))
      (node (ref "E22") (pin "13") (pinfunction "I1_13") (pintype "input"))
    )
    (net (code "59") (name "Net-(E20D-O)") (class "Default")
      (node (ref "E20") (pin "13") (pinfunction "O_13") (pintype "output"))
      (node (ref "E24") (pin "10") (pinfunction "I1_10") (pintype "input"))
    )
    (net (code "60") (name "Net-(E21A-O)") (class "Default")
      (node (ref "E21") (pin "2") (pinfunction "O_2") (pintype "output"))
      (node (ref "E22") (pin "5") (pinfunction "I1_5") (pintype "input"))
    )
    (net (code "61") (name "Net-(E21B-O)") (class "Default")
      (node (ref "E21") (pin "4") (pinfunction "O_4") (pintype "output"))
      (node (ref "E22") (pin "2") (pinfunction "I1_2") (pintype "input"))
    )
    (net (code "62") (name "Net-(E24A-O)") (class "Default")
      (node (ref "E24") (pin "3") (pinfunction "O_3") (pintype "output"))
      (node (ref "E25") (pin "15") (pinfunction "A_15") (pintype "input"))
    )
    (net (code "63") (name "Net-(E24B-O)") (class "Default")
      (node (ref "E24") (pin "2") (pinfunction "O_2") (pintype "output"))
      (node (ref "E25") (pin "14") (pinfunction "B_14") (pintype "input"))
    )
    (net (code "64") (name "Net-(E24C-O)") (class "Default")
      (node (ref "E24") (pin "14") (pinfunction "O_14") (pintype "output"))
      (node (ref "E28") (pin "9") (pinfunction "I_9") (pintype "input"))
    )
    (net (code "65") (name "Net-(E24D-O)") (class "Default")
      (node (ref "E24") (pin "13") (pinfunction "O_13") (pintype "output"))
      (node (ref "E25") (pin "1") (pinfunction "C_1") (pintype "input"))
    )
    (net (code "66") (name "Net-(E26B-O)") (class "Default")
      (node (ref "E26") (pin "6") (pinfunction "O_6") (pintype "output"))
      (node (ref "E28") (pin "13") (pinfunction "I_13") (pintype "input"))
    )
    (net (code "67") (name "Net-(E26C-O)") (class "Default")
      (node (ref "E26") (pin "12") (pinfunction "I0_12") (pintype "input"))
      (node (ref "E26") (pin "8") (pinfunction "O_8") (pintype "output"))
    )
    (net (code "68") (name "Net-(E27D-O)") (class "Default")
      (node (ref "E27") (pin "11") (pinfunction "O_11") (pintype "output"))
      (node (ref "E28") (pin "3") (pinfunction "I_3") (pintype "input"))
      (node (ref "S1") (pin "1") (pinfunction "A1_1") (pintype "bidirectional"))
    )
    (net (code "69") (name "Net-(E28B-O)") (class "Default")
      (node (ref "E28") (pin "4") (pinfunction "O_4") (pintype "open_collector"))
      (node (ref "R13") (pin "1") (pinfunction "1_1") (pintype "passive"))
      (node (ref "S1") (pin "3") (pinfunction "A3_3") (pintype "bidirectional"))
    )
    (net (code "70") (name "Net-(Q1-B)") (class "Default")
      (node (ref "Q1") (pin "2") (pinfunction "B_2") (pintype "passive"))
      (node (ref "R14") (pin "2") (pinfunction "2_2") (pintype "passive"))
    )
    (net (code "71") (name "Net-(R10-Pad1)") (class "Default")
      (node (ref "R10") (pin "1") (pinfunction "1_1") (pintype "passive"))
      (node (ref "W4") (pin "2") (pinfunction "2_2") (pintype "passive"))
    )
    (net (code "72") (name "Net-(S2-A1)") (class "Default")
      (node (ref "C39") (pin "1") (pinfunction "1_1") (pintype "passive"))
      (node (ref "S2") (pin "1") (pinfunction "A1_1") (pintype "bidirectional"))
    )
    (net (code "73") (name "Net-(S2-A3)") (class "Default")
      (node (ref "C38") (pin "1") (pinfunction "1_1") (pintype "passive"))
      (node (ref "S2") (pin "3") (pinfunction "A3_3") (pintype "bidirectional"))
    )
    (net (code "74") (name "RED_DELAY") (class "Default")
      (node (ref "E2") (pin "5") (pinfunction "Q_5") (pintype "output"))
      (node (ref "E3") (pin "2") (pinfunction "I0_2") (pintype "input"))
      (node (ref "E3") (pin "9") (pinfunction "I1_9") (pintype "input"))
      (node (ref "TP1") (pin "TP") (pinfunction "TP_TP") (pintype "input"))
    )
    (net (code "75") (name "SET_DONE") (class "Default")
      (node (ref "E1") (pin "5") (pinfunction "Q_5") (pintype "output"))
      (node (ref "E3") (pin "6") (pinfunction "I1_6") (pintype "input"))
    )
    (net (code "76") (name "STORE") (class "Default")
      (node (ref "E5") (pin "9") (pinfunction "Q_9") (pintype "output"))
      (node (ref "E8") (pin "3") (pinfunction "I1_3") (pintype "input"))
    )
    (net (code "77") (name "TP3") (class "Default")
      (node (ref "E13") (pin "9") (pinfunction "I0_9") (pintype "input"))
      (node (ref "OMNIBUS") (pin "CH2") (pinfunction "1_CH2") (pintype "bidirectional"))
    )
    (net (code "78") (name "VCC") (class "Default")
      (node (ref "C1") (pin "1") (pinfunction "1_1") (pintype "passive"))
      (node (ref "C10") (pin "1") (pinfunction "1_1") (pintype "passive"))
      (node (ref "C11") (pin "1") (pinfunction "1_1") (pintype "passive"))
      (node (ref "C12") (pin "1") (pinfunction "1_1") (pintype "passive"))
      (node (ref "C13") (pin "1") (pinfunction "1_1") (pintype "passive"))
      (node (ref "C14") (pin "1") (pinfunction "1_1") (pintype "passive"))
      (node (ref "C15") (pin "1") (pinfunction "1_1") (pintype "passive"))
      (node (ref "C16") (pin "1") (pinfunction "1_1") (pintype "passive"))
      (node (ref "C17") (pin "1") (pinfunction "1_1") (pintype "passive"))
      (node (ref "C18") (pin "1") (pinfunction "1_1") (pintype "passive"))
      (node (ref "C19") (pin "1") (pinfunction "1_1") (pintype "passive"))
      (node (ref "C2") (pin "1") (pinfunction "1_1") (pintype "passive"))
      (node (ref "C20") (pin "1") (pinfunction "1_1") (pintype "passive"))
      (node (ref "C21") (pin "1") (pinfunction "1_1") (pintype "passive"))
      (node (ref "C22") (pin "1") (pinfunction "1_1") (pintype "passive"))
      (node (ref "C23") (pin "1") (pinfunction "1_1") (pintype "passive"))
      (node (ref "C24") (pin "1") (pinfunction "1_1") (pintype "passive"))
      (node (ref "C25") (pin "1") (pinfunction "1_1") (pintype "passive"))
      (node (ref "C26") (pin "1") (pinfunction "1_1") (pintype "passive"))
      (node (ref "C27") (pin "1") (pinfunction "1_1") (pintype "passive"))
      (node (ref "C28") (pin "1") (pinfunction "1_1") (pintype "passive"))
      (node (ref "C29") (pin "+") (pinfunction "+_+") (pintype "passive"))
      (node (ref "C3") (pin "1") (pinfunction "1_1") (pintype "passive"))
      (node (ref "C30") (pin "+") (pinfunction "+_+") (pintype "passive"))
      (node (ref "C31") (pin "+") (pinfunction "+_+") (pintype "passive"))
      (node (ref "C32") (pin "+") (pinfunction "+_+") (pintype "passive"))
      (node (ref "C4") (pin "1") (pinfunction "1_1") (pintype "passive"))
      (node (ref "C5") (pin "1") (pinfunction "1_1") (pintype "passive"))
      (node (ref "C6") (pin "1") (pinfunction "1_1") (pintype "passive"))
      (node (ref "C7") (pin "1") (pinfunction "1_1") (pintype "passive"))
      (node (ref "C8") (pin "1") (pinfunction "1_1") (pintype "passive"))
      (node (ref "C9") (pin "1") (pinfunction "1_1") (pintype "passive"))
      (node (ref "OMNIBUS") (pin "AA2") (pinfunction "1_AA2") (pintype "bidirectional"))
      (node (ref "OMNIBUS") (pin "BA2") (pinfunction "1_BA2") (pintype "bidirectional"))
      (node (ref "OMNIBUS") (pin "CA2") (pinfunction "1_CA2") (pintype "bidirectional"))
      (node (ref "R1") (pin "2") (pinfunction "2_2") (pintype "passive"))
      (node (ref "R10") (pin "2") (pinfunction "2_2") (pintype "passive"))
      (node (ref "R11") (pin "2") (pinfunction "2_2") (pintype "passive"))
      (node (ref "R12") (pin "2") (pinfunction "2_2") (pintype "passive"))
      (node (ref "R13") (pin "2") (pinfunction "2_2") (pintype "passive"))
      (node (ref "R15") (pin "2") (pinfunction "2_2") (pintype "passive"))
      (node (ref "R16") (pin "2") (pinfunction "2_2") (pintype "passive"))
      (node (ref "R17") (pin "2") (pinfunction "2_2") (pintype "passive"))
      (node (ref "R18") (pin "2") (pinfunction "2_2") (pintype "passive"))
      (node (ref "R19") (pin "2") (pinfunction "2_2") (pintype "passive"))
      (node (ref "R2") (pin "2") (pinfunction "2_2") (pintype "passive"))
      (node (ref "R20") (pin "2") (pinfunction "2_2") (pintype "passive"))
      (node (ref "R21") (pin "2") (pinfunction "2_2") (pintype "passive"))
      (node (ref "R22") (pin "2") (pinfunction "2_2") (pintype "passive"))
      (node (ref "R3") (pin "2") (pinfunction "2_2") (pintype "passive"))
      (node (ref "R4") (pin "2") (pinfunction "2_2") (pintype "passive"))
      (node (ref "R5") (pin "2") (pinfunction "2_2") (pintype "passive"))
      (node (ref "R6") (pin "2") (pinfunction "2_2") (pintype "passive"))
      (node (ref "R7") (pin "2") (pinfunction "2_2") (pintype "passive"))
      (node (ref "R8") (pin "2") (pinfunction "2_2") (pintype "passive"))
      (node (ref "R9") (pin "2") (pinfunction "2_2") (pintype "passive"))
    )
    (net (code "79") (name "WRITE_THRU") (class "Default")
      (node (ref "E10") (pin "9") (pinfunction "I_9") (pintype "input"))
      (node (ref "E5") (pin "5") (pinfunction "Q_5") (pintype "output"))
      (node (ref "E8") (pin "12") (pinfunction "I1_12") (pintype "input"))
    )
    (net (code "80") (name "Z_PULSE") (class "Default")
      (node (ref "E27") (pin "12") (pinfunction "I0_12") (pintype "input"))
      (node (ref "F") (pin "A2") (pinfunction "P_A2") (pintype "passive"))
      (node (ref "R11") (pin "1") (pinfunction "1_1") (pintype "passive"))
    )
    (net (code "81") (name "unconnected-(E1A-~{Q}-Pad4)") (class "Default")
      (node (ref "E1") (pin "4") (pinfunction "~{Q}_4") (pintype "output"))
    )
    (net (code "82") (name "unconnected-(E2A-~{Q}-Pad4)") (class "Default")
      (node (ref "E2") (pin "4") (pinfunction "~{Q}_4") (pintype "output"))
    )
    (net (code "83") (name "unconnected-(E2B-~{Q}-Pad12)") (class "Default")
      (node (ref "E2") (pin "12") (pinfunction "~{Q}_12") (pintype "output"))
    )
    (net (code "84") (name "unconnected-(E4A-Q-Pad8)") (class "Default")
      (node (ref "E4") (pin "8") (pinfunction "Q_8") (pintype "output"))
    )
    (net (code "85") (name "unconnected-(E5A-~{Q}-Pad6)") (class "Default")
      (node (ref "E5") (pin "6") (pinfunction "~{Q}_6") (pintype "output"))
    )
    (net (code "86") (name "unconnected-(E6A-~{Q}-Pad6)") (class "Default")
      (node (ref "E6") (pin "6") (pinfunction "~{Q}_6") (pintype "output"))
    )
    (net (code "87") (name "unconnected-(E15A-Q-Pad8)") (class "Default")
      (node (ref "E15") (pin "8") (pinfunction "Q_8") (pintype "output"))
    )
    (net (code "88") (name "unconnected-(E18A-~{Q}-Pad6)") (class "Default")
      (node (ref "E18") (pin "6") (pinfunction "~{Q}_6") (pintype "output"))
    )
    (net (code "89") (name "unconnected-(E18B-~{Q}-Pad8)") (class "Default")
      (node (ref "E18") (pin "8") (pinfunction "~{Q}_8") (pintype "output"))
    )
    (net (code "90") (name "unconnected-(E19A-~{Q}-Pad6)") (class "Default")
      (node (ref "E19") (pin "6") (pinfunction "~{Q}_6") (pintype "output"))
    )
    (net (code "91") (name "unconnected-(E25A-8-Pad6)") (class "Default")
      (node (ref "E25") (pin "6") (pinfunction "8_6") (pintype "output"))
    )
    (net (code "92") (name "unconnected-(E25A-9-Pad7)") (class "Default")
      (node (ref "E25") (pin "7") (pinfunction "9_7") (pintype "output"))
    )
    (net (code "93") (name "~{BTP3}") (class "Default")
      (node (ref "E13") (pin "14") (pinfunction "O_14") (pintype "output"))
      (node (ref "E14") (pin "9") (pinfunction "I_9") (pintype "input"))
      (node (ref "E20") (pin "12") (pinfunction "I1_12") (pintype "input"))
      (node (ref "E20") (pin "3") (pinfunction "I1_3") (pintype "input"))
    )
    (net (code "94") (name "~{B_DICD}") (class "Default")
      (node (ref "E22") (pin "3") (pinfunction "O_3") (pintype "output"))
      (node (ref "E23") (pin "5") (pinfunction "I3_5") (pintype "input"))
    )
    (net (code "95") (name "~{B_DIXY}") (class "Default")
      (node (ref "E15") (pin "1") (pinfunction "P$1_1") (pintype "input"))
      (node (ref "E15") (pin "2") (pinfunction "P$2_2") (pintype "input"))
      (node (ref "E22") (pin "6") (pinfunction "O_6") (pintype "output"))
      (node (ref "E23") (pin "4") (pinfunction "I2_4") (pintype "input"))
    )
    (net (code "96") (name "~{B_LOAD_EN}") (class "Default")
      (node (ref "E23") (pin "2") (pinfunction "I1_2") (pintype "input"))
      (node (ref "E26") (pin "11") (pinfunction "O_11") (pintype "output"))
    )
    (net (code "97") (name "~{C0}") (class "Default")
      (node (ref "E16") (pin "10") (pinfunction "O_10") (pintype "open_collector"))
      (node (ref "OMNIBUS") (pin "CE1") (pinfunction "1_CE1") (pintype "bidirectional"))
    )
    (net (code "98") (name "~{C1}") (class "Default")
      (node (ref "E16") (pin "13") (pinfunction "O_13") (pintype "open_collector"))
      (node (ref "OMNIBUS") (pin "CH1") (pinfunction "1_CH1") (pintype "bidirectional"))
    )
    (net (code "99") (name "~{CHAN}") (class "Default")
      (node (ref "E28") (pin "2") (pinfunction "O_2") (pintype "open_collector"))
      (node (ref "F") (pin "R1") (pinfunction "P_R1") (pintype "passive"))
      (node (ref "R12") (pin "1") (pinfunction "1_1") (pintype "passive"))
    )
    (net (code "100") (name "~{CLEAR_DONE}") (class "Default")
      (node (ref "E26") (pin "10") (pinfunction "I1_10") (pintype "input"))
      (node (ref "E3") (pin "13") (pinfunction "O_13") (pintype "output"))
    )
    (net (code "101") (name "~{CLEAR}") (class "Default")
      (node (ref "E18") (pin "1") (pinfunction "CLR_1") (pintype "input"))
      (node (ref "E18") (pin "13") (pinfunction "CLR_13") (pintype "input"))
      (node (ref "E23") (pin "1") (pinfunction "I0_1") (pintype "input"))
      (node (ref "E28") (pin "6") (pinfunction "O_6") (pintype "open_collector"))
      (node (ref "E5") (pin "1") (pinfunction "CLR_1") (pintype "input"))
      (node (ref "E5") (pin "13") (pinfunction "CLR_13") (pintype "input"))
      (node (ref "E6") (pin "13") (pinfunction "CLR_13") (pintype "input"))
      (node (ref "R5") (pin "1") (pinfunction "1_1") (pintype "passive"))
    )
    (net (code "102") (name "~{CL_DONE}") (class "Default")
      (node (ref "E19") (pin "1") (pinfunction "CLR_1") (pintype "input"))
      (node (ref "E23") (pin "6") (pinfunction "O_6") (pintype "output"))
    )
    (net (code "103") (name "~{COLOR}") (class "Default")
      (node (ref "E10") (pin "11") (pinfunction "I_11") (pintype "input"))
      (node (ref "E2") (pin "2") (pinfunction "B_2") (pintype "input"))
      (node (ref "E6") (pin "8") (pinfunction "~{Q}_8") (pintype "output"))
      (node (ref "E7") (pin "6") (pinfunction "I1_6") (pintype "input"))
    )
    (net (code "104") (name "~{COL_RED}") (class "Default")
      (node (ref "E7") (pin "1") (pinfunction "O_1") (pintype "open_collector"))
      (node (ref "F") (pin "L1") (pinfunction "P_L1") (pintype "passive"))
      (node (ref "R21") (pin "1") (pinfunction "1_1") (pintype "passive"))
    )
    (net (code "105") (name "~{DATA00}") (class "Default")
      (node (ref "E17") (pin "13") (pinfunction "O_13") (pintype "open_collector"))
      (node (ref "OMNIBUS") (pin "AR1") (pinfunction "1_AR1") (pintype "bidirectional"))
    )
    (net (code "106") (name "~{DATA06}") (class "Default")
      (node (ref "E8") (pin "13") (pinfunction "O_13") (pintype "open_collector"))
      (node (ref "E9") (pin "9") (pinfunction "I0_9") (pintype "input"))
      (node (ref "OMNIBUS") (pin "BU1") (pinfunction "1_BU1") (pintype "bidirectional"))
    )
    (net (code "107") (name "~{DATA07}") (class "Default")
      (node (ref "E8") (pin "1") (pinfunction "O_1") (pintype "open_collector"))
      (node (ref "E9") (pin "7") (pinfunction "I1_7") (pintype "input"))
      (node (ref "OMNIBUS") (pin "BV1") (pinfunction "1_BV1") (pintype "bidirectional"))
    )
    (net (code "108") (name "~{DATA08}") (class "Default")
      (node (ref "E9") (pin "4") (pinfunction "I0_4") (pintype "input"))
      (node (ref "OMNIBUS") (pin "DR1") (pinfunction "1_DR1") (pintype "bidirectional"))
    )
    (net (code "109") (name "~{DATA09}") (class "Default")
      (node (ref "E8") (pin "10") (pinfunction "O_10") (pintype "open_collector"))
      (node (ref "E9") (pin "12") (pinfunction "I1_12") (pintype "input"))
      (node (ref "OMNIBUS") (pin "DS1") (pinfunction "1_DS1") (pintype "bidirectional"))
    )
    (net (code "110") (name "~{DATA10}") (class "Default")
      (node (ref "E13") (pin "4") (pinfunction "I0_4") (pintype "input"))
      (node (ref "E16") (pin "1") (pinfunction "O_1") (pintype "open_collector"))
      (node (ref "OMNIBUS") (pin "DU1") (pinfunction "1_DU1") (pintype "bidirectional"))
    )
    (net (code "111") (name "~{DATA11}") (class "Default")
      (node (ref "E13") (pin "6") (pinfunction "I0_6") (pintype "input"))
      (node (ref "E16") (pin "4") (pinfunction "O_4") (pintype "open_collector"))
      (node (ref "OMNIBUS") (pin "DV1") (pinfunction "1_DV1") (pintype "bidirectional"))
    )
    (net (code "112") (name "~{DEL_1}") (class "Default")
      (node (ref "E15") (pin "6") (pinfunction "~{Q}_6") (pintype "output"))
      (node (ref "E23") (pin "9") (pinfunction "I0_9") (pintype "input"))
      (node (ref "E27") (pin "13") (pinfunction "I1_13") (pintype "input"))
    )
    (net (code "113") (name "~{DICD}") (class "Default")
      (node (ref "E21") (pin "3") (pinfunction "I_3") (pintype "input"))
      (node (ref "E25") (pin "12") (pinfunction "1_12") (pintype "output"))
    )
    (net (code "114") (name "~{DICL}") (class "Default")
      (node (ref "E20") (pin "11") (pinfunction "I0_11") (pintype "input"))
      (node (ref "E25") (pin "13") (pinfunction "0_13") (pintype "output"))
    )
    (net (code "115") (name "~{DILE}") (class "Default")
      (node (ref "E20") (pin "2") (pinfunction "I0_2") (pintype "input"))
      (node (ref "E25") (pin "4") (pinfunction "6_4") (pintype "output"))
      (node (ref "E26") (pin "1") (pinfunction "I0_1") (pintype "input"))
      (node (ref "E26") (pin "4") (pinfunction "I0_4") (pintype "input"))
      (node (ref "F") (pin "P1") (pinfunction "P_P1") (pintype "passive"))
    )
    (net (code "116") (name "~{DILX}") (class "Default")
      (node (ref "E21") (pin "11") (pinfunction "I_11") (pintype "input"))
      (node (ref "E25") (pin "10") (pinfunction "3_10") (pintype "output"))
    )
    (net (code "117") (name "~{DILY}") (class "Default")
      (node (ref "E21") (pin "9") (pinfunction "I_9") (pintype "input"))
      (node (ref "E25") (pin "9") (pinfunction "4_9") (pintype "output"))
    )
    (net (code "118") (name "~{DIRE}") (class "Default")
      (node (ref "E21") (pin "13") (pinfunction "I_13") (pintype "input"))
      (node (ref "E25") (pin "5") (pinfunction "7_5") (pintype "output"))
      (node (ref "E26") (pin "2") (pinfunction "I1_2") (pintype "input"))
      (node (ref "F") (pin "B2") (pinfunction "P_B2") (pintype "passive"))
    )
    (net (code "119") (name "~{DISD}") (class "Default")
      (node (ref "E21") (pin "5") (pinfunction "I_5") (pintype "input"))
      (node (ref "E25") (pin "11") (pinfunction "2_11") (pintype "output"))
    )
    (net (code "120") (name "~{DIXY}") (class "Default")
      (node (ref "E21") (pin "1") (pinfunction "I_1") (pintype "input"))
      (node (ref "E25") (pin "3") (pinfunction "5_3") (pintype "output"))
    )
    (net (code "121") (name "~{DLY_DONE}") (class "Default")
      (node (ref "E23") (pin "12") (pinfunction "I2_12") (pintype "input"))
      (node (ref "E3") (pin "1") (pinfunction "O_1") (pintype "output"))
    )
    (net (code "122") (name "~{ERASE_INTERVAL}") (class "Default")
      (node (ref "F") (pin "D2") (pinfunction "P_D2") (pintype "passive"))
      (node (ref "R14") (pin "1") (pinfunction "1_1") (pintype "passive"))
    )
    (net (code "123") (name "~{ERASE}") (class "Default")
      (node (ref "E10") (pin "4") (pinfunction "O_4") (pintype "open_collector"))
      (node (ref "F") (pin "K1") (pinfunction "P_K1") (pintype "passive"))
    )
    (net (code "124") (name "~{INTERNAL_IO}") (class "Default")
      (node (ref "E17") (pin "10") (pinfunction "O_10") (pintype "open_collector"))
      (node (ref "OMNIBUS") (pin "CL1") (pinfunction "1_CL1") (pintype "bidirectional"))
    )
    (net (code "125") (name "~{INTERRUPT}") (class "Default")
      (node (ref "E17") (pin "4") (pinfunction "O_4") (pintype "open_collector"))
      (node (ref "OMNIBUS") (pin "CP1") (pinfunction "1_CP1") (pintype "bidirectional"))
    )
    (net (code "126") (name "~{IOT}") (class "Default")
      (node (ref "E24") (pin "12") (pinfunction "I1_12") (pintype "input"))
      (node (ref "E24") (pin "5") (pinfunction "I1_5") (pintype "input"))
      (node (ref "E24") (pin "6") (pinfunction "I0_6") (pintype "input"))
      (node (ref "E25") (pin "2") (pinfunction "D_2") (pintype "input"))
      (node (ref "E28") (pin "10") (pinfunction "O_10") (pintype "open_collector"))
      (node (ref "R2") (pin "1") (pinfunction "1_1") (pintype "passive"))
    )
    (net (code "127") (name "~{LD_DEL}") (class "Default")
      (node (ref "E23") (pin "13") (pinfunction "I3_13") (pintype "input"))
      (node (ref "E4") (pin "6") (pinfunction "~{Q}_6") (pintype "output"))
    )
    (net (code "128") (name "~{LOAD_DATA}") (class "Default")
      (node (ref "E13") (pin "5") (pinfunction "I1_5") (pintype "input"))
      (node (ref "E13") (pin "7") (pinfunction "I1_7") (pintype "input"))
      (node (ref "E28") (pin "12") (pinfunction "O_12") (pintype "open_collector"))
      (node (ref "E9") (pin "10") (pinfunction "I1_10") (pintype "input"))
      (node (ref "E9") (pin "11") (pinfunction "I0_11") (pintype "input"))
      (node (ref "E9") (pin "5") (pinfunction "I1_5") (pintype "input"))
      (node (ref "E9") (pin "6") (pinfunction "I0_6") (pintype "input"))
      (node (ref "R6") (pin "1") (pinfunction "1_1") (pintype "passive"))
    )
    (net (code "129") (name "~{LOAD_EN}") (class "Default")
      (node (ref "E20") (pin "10") (pinfunction "O_10") (pintype "output"))
      (node (ref "E26") (pin "5") (pinfunction "I1_5") (pintype "input"))
      (node (ref "E26") (pin "9") (pinfunction "I0_9") (pintype "input"))
      (node (ref "E4") (pin "1") (pinfunction "P$1_1") (pintype "input"))
      (node (ref "E4") (pin "2") (pinfunction "P$2_2") (pintype "input"))
      (node (ref "F") (pin "V1") (pinfunction "P_V1") (pintype "passive"))
    )
    (net (code "130") (name "~{MD3}") (class "Default")
      (node (ref "E11") (pin "12") (pinfunction "I1_12") (pintype "input"))
      (node (ref "OMNIBUS") (pin "AP1") (pinfunction "1_AP1") (pintype "bidirectional"))
    )
    (net (code "131") (name "~{MD4}") (class "Default")
      (node (ref "E11") (pin "9") (pinfunction "I0_9") (pintype "input"))
      (node (ref "OMNIBUS") (pin "BK1") (pinfunction "1_BK1") (pintype "bidirectional"))
    )
    (net (code "132") (name "~{MD5}") (class "Default")
      (node (ref "E11") (pin "4") (pinfunction "I0_4") (pintype "input"))
      (node (ref "OMNIBUS") (pin "BL1") (pinfunction "1_BL1") (pintype "bidirectional"))
      (node (ref "W2") (pin "1") (pinfunction "1_1") (pintype "passive"))
    )
    (net (code "133") (name "~{MD6}") (class "Default")
      (node (ref "E12") (pin "11") (pinfunction "I5_11") (pintype "input"))
      (node (ref "OMNIBUS") (pin "BM1") (pinfunction "1_BM1") (pintype "bidirectional"))
    )
    (net (code "134") (name "~{MD7}") (class "Default")
      (node (ref "E11") (pin "7") (pinfunction "I1_7") (pintype "input"))
      (node (ref "OMNIBUS") (pin "BP1") (pinfunction "1_BP1") (pintype "bidirectional"))
    )
    (net (code "135") (name "~{MD8}") (class "Default")
      (node (ref "E12") (pin "12") (pinfunction "I6_12") (pintype "input"))
      (node (ref "OMNIBUS") (pin "DK1") (pinfunction "1_DK1") (pintype "bidirectional"))
    )
    (net (code "136") (name "~{MD9}") (class "Default")
      (node (ref "E24") (pin "11") (pinfunction "I0_11") (pintype "input"))
      (node (ref "OMNIBUS") (pin "DL1") (pinfunction "1_DL1") (pintype "bidirectional"))
    )
    (net (code "137") (name "~{MD10}") (class "Default")
      (node (ref "E24") (pin "7") (pinfunction "I1_7") (pintype "input"))
      (node (ref "OMNIBUS") (pin "DM1") (pinfunction "1_DM1") (pintype "bidirectional"))
    )
    (net (code "138") (name "~{MD11}") (class "Default")
      (node (ref "E24") (pin "4") (pinfunction "I0_4") (pintype "input"))
      (node (ref "OMNIBUS") (pin "DP1") (pinfunction "1_DP1") (pintype "bidirectional"))
    )
    (net (code "139") (name "~{NON_STORE}") (class "Default")
      (node (ref "E10") (pin "12") (pinfunction "O_12") (pintype "open_collector"))
      (node (ref "F") (pin "C2") (pinfunction "P_C2") (pintype "passive"))
    )
    (net (code "140") (name "~{PAUSE}") (class "Default")
      (node (ref "E13") (pin "12") (pinfunction "I1_12") (pintype "input"))
      (node (ref "OMNIBUS") (pin "CD1") (pinfunction "1_CD1") (pintype "bidirectional"))
    )
    (net (code "141") (name "~{SET_DONE}") (class "Default")
      (node (ref "E1") (pin "12") (pinfunction "~{Q}_12") (pintype "output"))
      (node (ref "E23") (pin "10") (pinfunction "I1_10") (pintype "input"))
    )
    (net (code "142") (name "~{SKIP}") (class "Default")
      (node (ref "E17") (pin "1") (pinfunction "O_1") (pintype "open_collector"))
      (node (ref "OMNIBUS") (pin "CS1") (pinfunction "1_CS1") (pintype "bidirectional"))
    )
    (net (code "143") (name "~{STORE}") (class "Default")
      (node (ref "E10") (pin "13") (pinfunction "I_13") (pintype "input"))
      (node (ref "E5") (pin "8") (pinfunction "~{Q}_8") (pintype "output"))
      (node (ref "E7") (pin "5") (pinfunction "I0_5") (pintype "input"))
    )
    (net (code "144") (name "~{WRITE_THRU}") (class "Default")
      (node (ref "E10") (pin "8") (pinfunction "O_8") (pintype "open_collector"))
      (node (ref "F") (pin "M1") (pinfunction "P_M1") (pintype "passive"))
    )
  )
)
